# p2grv-001.net
KiCad netlist of a schematic drawn in EAGLE
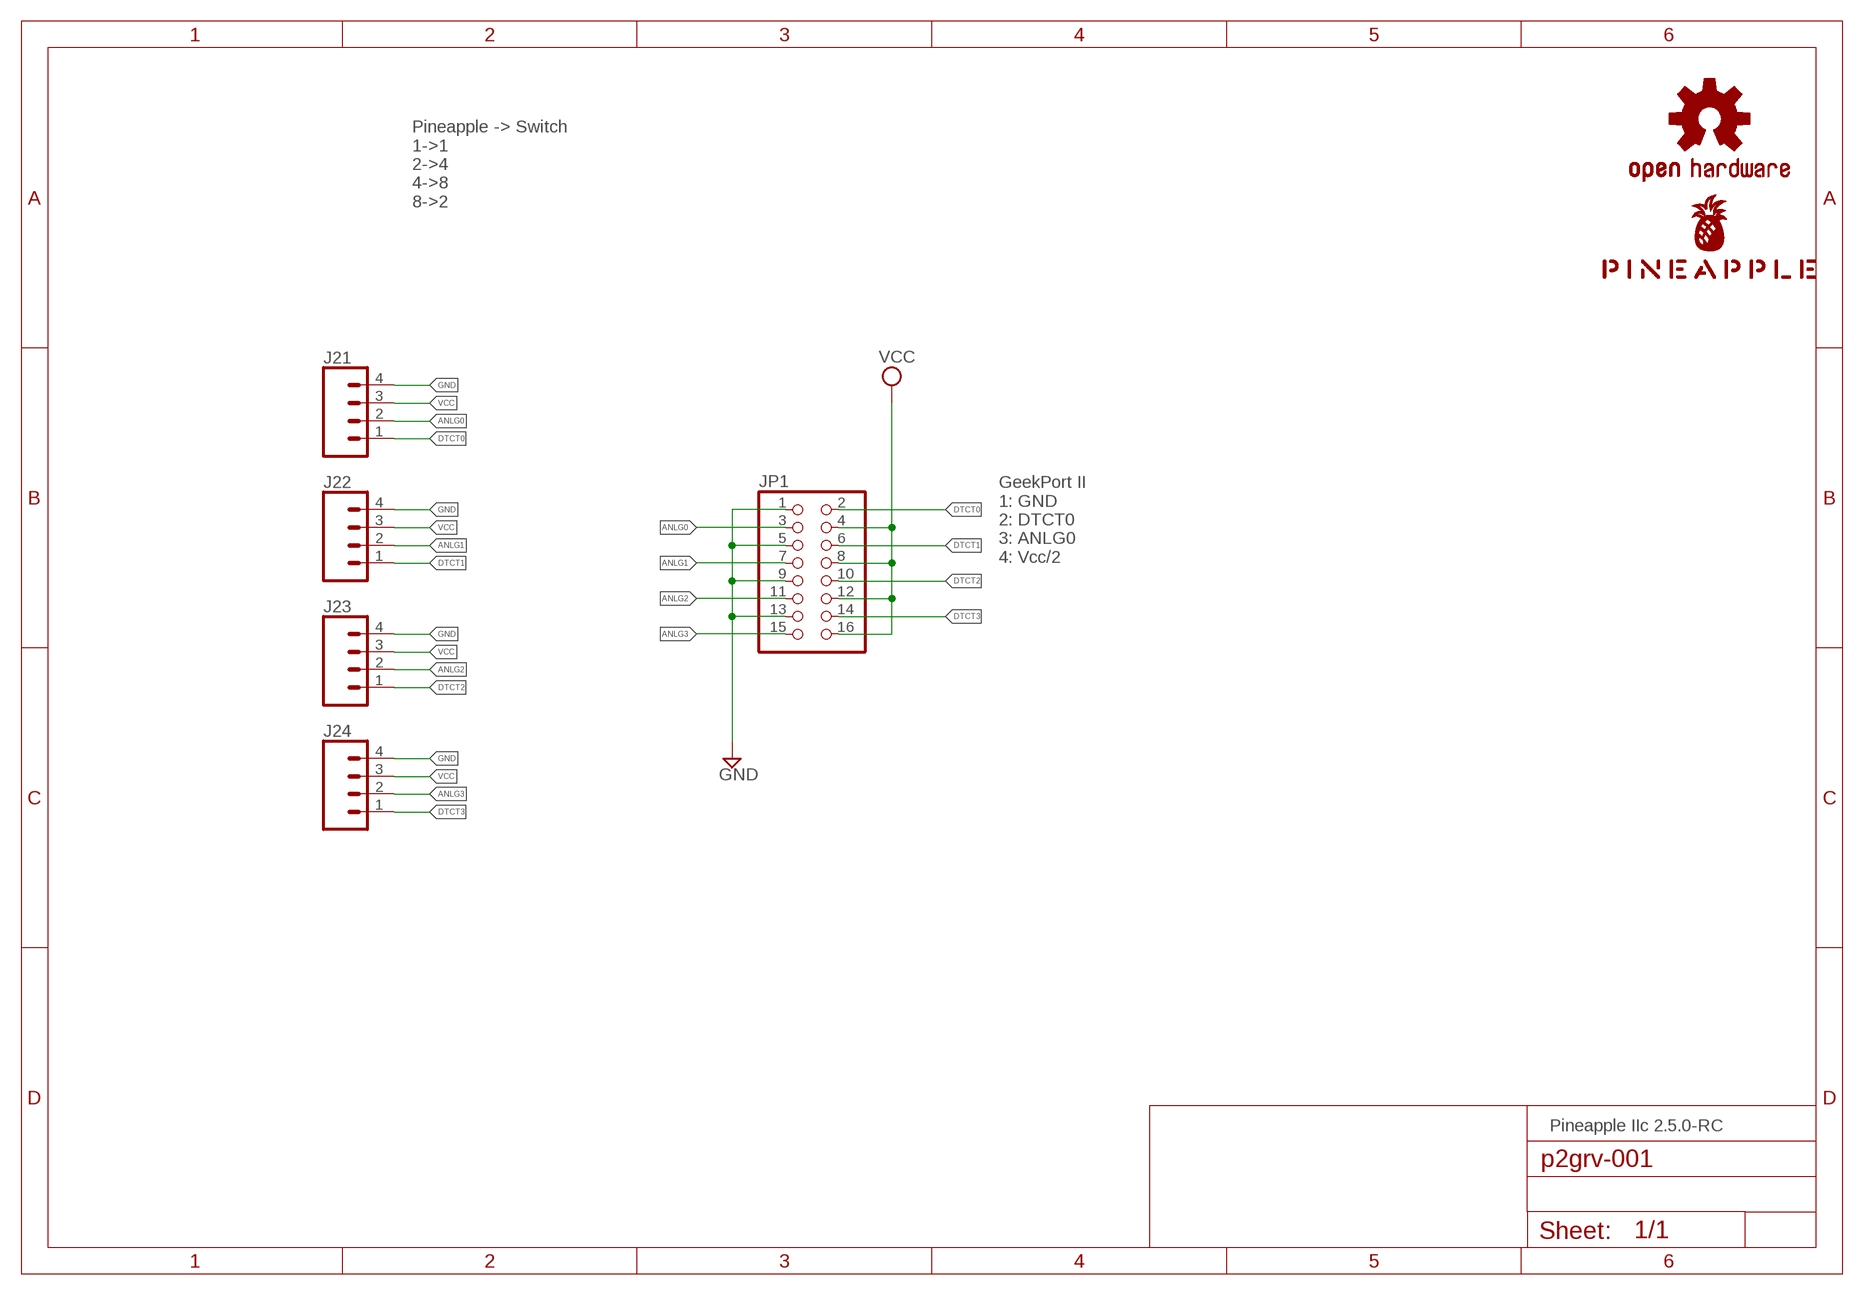
[diagram p0: schematic, sheet 1]

(export (version "E")
  (design (tool "Eeschema 10.0.6"))
  (components
    (comp (ref "J21")
      (value "CONN_04JST-PTH-VERT")
      (footprint "eagle-import:JST-4-PTH-VERT")
      (libsource (lib "eagle-import") (part "CONN_04JST-PTH-VERT"))
    )
    (comp (ref "J22")
      (value "CONN_04JST-PTH-VERT")
      (footprint "eagle-import:JST-4-PTH-VERT")
      (libsource (lib "eagle-import") (part "CONN_04JST-PTH-VERT"))
    )
    (comp (ref "J23")
      (value "CONN_04JST-PTH-VERT")
      (footprint "eagle-import:JST-4-PTH-VERT")
      (libsource (lib "eagle-import") (part "CONN_04JST-PTH-VERT"))
    )
    (comp (ref "J24")
      (value "CONN_04JST-PTH-VERT")
      (footprint "eagle-import:JST-4-PTH-VERT")
      (libsource (lib "eagle-import") (part "CONN_04JST-PTH-VERT"))
    )
    (comp (ref "JP1")
      (value "PINHD-2X8")
      (footprint "eagle-import:2X08")
      (libsource (lib "eagle-import") (part "PINHD-2X8"))
    )
    (comp (ref "LOGO1")
      (value "OSHW-LOGOS-COPPER")
      (footprint "eagle-import:OSHW-LOGO-S_COPPER")
      (libsource (lib "eagle-import") (part "OSHW-LOGOS-COPPER"))
    )
    (comp (ref "U$1")
      (value "PINEAPPLE450_SILK")
      (footprint "eagle-import:PINEAPPLE450_SILK")
      (libsource (lib "eagle-import") (part "PINEAPPLE450_SILK"))
    )
  )
  (nets
    (net (code "1") (name "ANLG0") (class "Default")
      (node (ref "J21") (pin "2") (pinfunction "2_2") (pintype "passive"))
      (node (ref "JP1") (pin "3") (pinfunction "3_3") (pintype "passive"))
    )
    (net (code "2") (name "ANLG1") (class "Default")
      (node (ref "J22") (pin "2") (pinfunction "2_2") (pintype "passive"))
      (node (ref "JP1") (pin "7") (pinfunction "7_7") (pintype "passive"))
    )
    (net (code "3") (name "ANLG2") (class "Default")
      (node (ref "J23") (pin "2") (pinfunction "2_2") (pintype "passive"))
      (node (ref "JP1") (pin "11") (pinfunction "11_11") (pintype "passive"))
    )
    (net (code "4") (name "ANLG3") (class "Default")
      (node (ref "J24") (pin "2") (pinfunction "2_2") (pintype "passive"))
      (node (ref "JP1") (pin "15") (pinfunction "15_15") (pintype "passive"))
    )
    (net (code "5") (name "DTCT0") (class "Default")
      (node (ref "J21") (pin "1") (pinfunction "1_1") (pintype "passive"))
      (node (ref "JP1") (pin "2") (pinfunction "2_2") (pintype "passive"))
    )
    (net (code "6") (name "DTCT1") (class "Default")
      (node (ref "J22") (pin "1") (pinfunction "1_1") (pintype "passive"))
      (node (ref "JP1") (pin "6") (pinfunction "6_6") (pintype "passive"))
    )
    (net (code "7") (name "DTCT2") (class "Default")
      (node (ref "J23") (pin "1") (pinfunction "1_1") (pintype "passive"))
      (node (ref "JP1") (pin "10") (pinfunction "10_10") (pintype "passive"))
    )
    (net (code "8") (name "DTCT3") (class "Default")
      (node (ref "J24") (pin "1") (pinfunction "1_1") (pintype "passive"))
      (node (ref "JP1") (pin "14") (pinfunction "14_14") (pintype "passive"))
    )
    (net (code "9") (name "GND") (class "Default")
      (node (ref "J21") (pin "4") (pinfunction "4_4") (pintype "passive"))
      (node (ref "J22") (pin "4") (pinfunction "4_4") (pintype "passive"))
      (node (ref "J23") (pin "4") (pinfunction "4_4") (pintype "passive"))
      (node (ref "J24") (pin "4") (pinfunction "4_4") (pintype "passive"))
      (node (ref "JP1") (pin "1") (pinfunction "1_1") (pintype "passive"))
      (node (ref "JP1") (pin "13") (pinfunction "13_13") (pintype "passive"))
      (node (ref "JP1") (pin "5") (pinfunction "5_5") (pintype "passive"))
      (node (ref "JP1") (pin "9") (pinfunction "9_9") (pintype "passive"))
    )
    (net (code "10") (name "VCC") (class "Default")
      (node (ref "J21") (pin "3") (pinfunction "3_3") (pintype "passive"))
      (node (ref "J22") (pin "3") (pinfunction "3_3") (pintype "passive"))
      (node (ref "J23") (pin "3") (pinfunction "3_3") (pintype "passive"))
      (node (ref "J24") (pin "3") (pinfunction "3_3") (pintype "passive"))
      (node (ref "JP1") (pin "12") (pinfunction "12_12") (pintype "passive"))
      (node (ref "JP1") (pin "16") (pinfunction "16_16") (pintype "passive"))
      (node (ref "JP1") (pin "4") (pinfunction "4_4") (pintype "passive"))
      (node (ref "JP1") (pin "8") (pinfunction "8_8") (pintype "passive"))
    )
  )
)
